# P14_ETH2_RGMII.net
KiCad netlist of a schematic drawn in Altium Designer
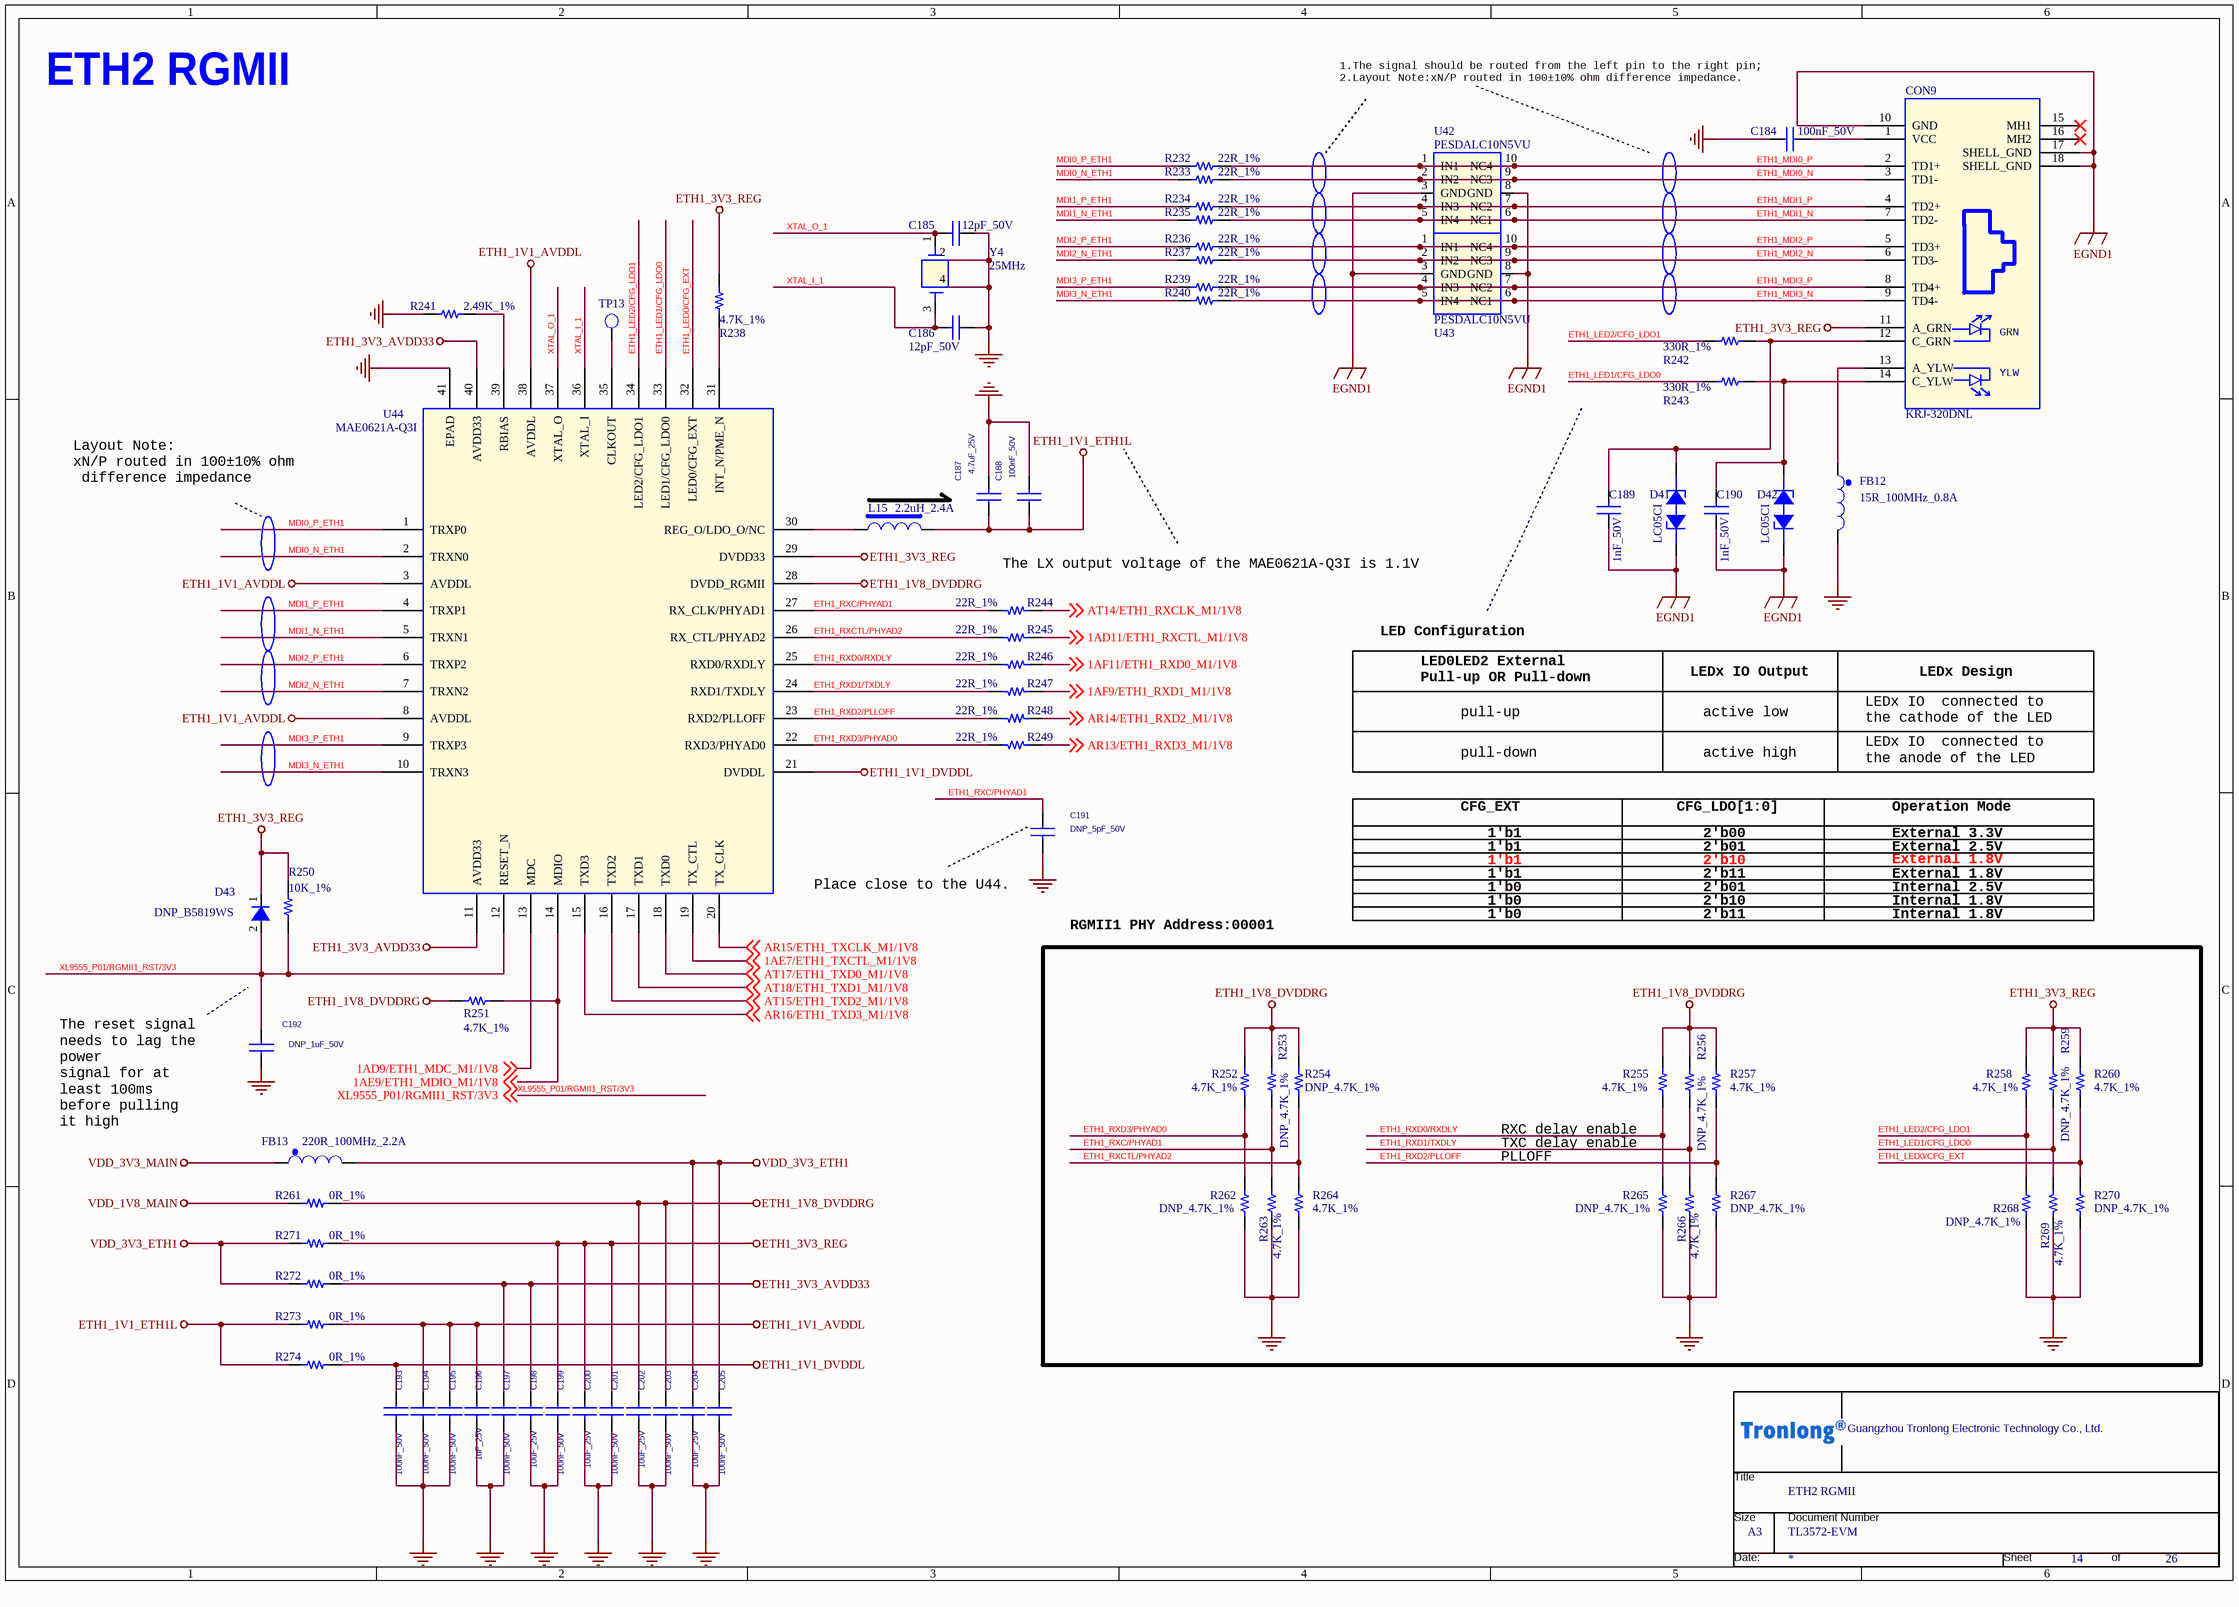
[diagram p0: P14_ETH2 RGMII.SchDoc]

(export (version "E")
  (design (tool "Eeschema 10.0.6"))
  (components
    (comp (ref "*")
      (value "Tronlong_TITTLE_20211115")
      (fields
        (field (name "DOC") "TL3572-EVM")
        (field (name "TITLE") "ETH2 RGMII")
        (field (name "ORGNAME") "Guangzhou Tronlong Electronic Technology Co., Ltd.")
        (field (name "PAGE SIZE") "A3")
        (field (name "PAGE NUMBER") "14")
        (field (name "PAGE COUNT") "26")
      )
      (libsource (lib "*") (part "Tronlong_TITTLE_20211115"))
    )
    (comp (ref "C184")
      (value "100nF_50V")
      (footprint "C0402")
      (description "贴片陶瓷电容,100nF,10%,50V,X7R")
      (fields
        (field (name "MANUFACTURER PARTNUMBER") "0402B104K500NT")
        (field (name "MANUFACTURER") "广东风华高新科技股份有限公司（FH）")
      )
      (libsource (lib "*") (part "CAP NP_Dup2"))
    )
    (comp (ref "C185")
      (value "12pF_50V")
      (footprint "C0402")
      (description "贴片陶瓷电容,12pF,5%,50V,COG")
      (fields
        (field (name "MANUFACTURER") "广东风华高新科技股份有限公司（FH）")
        (field (name "MANUFACTURER PARTNUMBER") "0402CG120J500NT")
      )
      (libsource (lib "*") (part "CAP NP_Dup2"))
    )
    (comp (ref "C186")
      (value "12pF_50V")
      (footprint "C0402")
      (description "贴片陶瓷电容,12pF,5%,50V,COG")
      (fields
        (field (name "MANUFACTURER PARTNUMBER") "0402CG120J500NT")
        (field (name "MANUFACTURER") "广东风华高新科技股份有限公司（FH）")
      )
      (libsource (lib "*") (part "CAP NP_Dup2"))
    )
    (comp (ref "C187")
      (value "4.7uF_25V")
      (footprint "C0603")
      (description "贴片陶瓷电容,4.7uF,10%,25V,X5R")
      (fields
        (field (name "MANUFACTURER PARTNUMBER") "0603X475K250NT")
        (field (name "MANUFACTURER") "广东风华高新科技股份有限公司（FH）")
      )
      (libsource (lib "*") (part "CAP NP_Dup2"))
    )
    (comp (ref "C188")
      (value "100nF_50V")
      (footprint "C0402")
      (description "贴片陶瓷电容,100nF,10%,50V,X7R")
      (fields
        (field (name "MANUFACTURER") "广东风华高新科技股份有限公司（FH）")
        (field (name "MANUFACTURER PARTNUMBER") "0402B104K500NT")
      )
      (libsource (lib "*") (part "CAP NP_Dup2"))
    )
    (comp (ref "C189")
      (value "1nF_50V")
      (footprint "C0402")
      (description "贴片陶瓷电容,1nF,10%,50V,X7R")
      (fields
        (field (name "TOLERANCE") "±10%")
        (field (name "MANUFACTURER") "广东风华高新科技股份有限公司（FH）")
        (field (name "CREATED BY") "JJJ")
      )
      (libsource (lib "*") (part "CAP NP_1"))
    )
    (comp (ref "C190")
      (value "1nF_50V")
      (footprint "C0402")
      (description "贴片陶瓷电容,1nF,10%,50V,X7R")
      (fields
        (field (name "TOLERANCE") "±10%")
        (field (name "MANUFACTURER") "广东风华高新科技股份有限公司（FH）")
        (field (name "CREATED BY") "JJJ")
      )
      (libsource (lib "*") (part "CAP NP_1"))
    )
    (comp (ref "C191")
      (value "DNP_5pF_50V")
      (footprint "C0402")
      (description "贴片陶瓷电容,22pF,5%,50V,COG")
      (fields
        (field (name "MANUFACTURER PARTNUMBER") "0402CG220J500NT")
        (field (name "MANUFACTURER") "广东风华高新科技股份有限公司（FH）")
      )
      (libsource (lib "*") (part "CAP NP_Dup2"))
    )
    (comp (ref "C192")
      (value "DNP_1uF_50V")
      (footprint "C0603")
      (description "贴片陶瓷电容,1uF,10%,50V,X5R")
      (fields
        (field (name "MANUFACTURER PARTNUMBER") "0603X105K500NT")
        (field (name "MANUFACTURER") "广东风华高新科技股份有限公司（FH）")
      )
      (libsource (lib "*") (part "CAP NP_Dup2"))
    )
    (comp (ref "C193")
      (value "100nF_50V")
      (footprint "C0402")
      (description "贴片陶瓷电容,100nF,10%,50V,X7R")
      (fields
        (field (name "MANUFACTURER") "广东风华高新科技股份有限公司（FH）")
        (field (name "MANUFACTURER PARTNUMBER") "0402B104K500NT")
      )
      (libsource (lib "*") (part "CAP NP_Dup2"))
    )
    (comp (ref "C194")
      (value "100nF_50V")
      (footprint "C0402")
      (description "贴片陶瓷电容,100nF,10%,50V,X7R")
      (fields
        (field (name "MANUFACTURER PARTNUMBER") "0402B104K500NT")
        (field (name "MANUFACTURER") "广东风华高新科技股份有限公司（FH）")
      )
      (libsource (lib "*") (part "CAP NP_Dup2"))
    )
    (comp (ref "C195")
      (value "100nF_50V")
      (footprint "C0402")
      (description "贴片陶瓷电容,100nF,10%,50V,X7R")
      (fields
        (field (name "MANUFACTURER") "广东风华高新科技股份有限公司（FH）")
        (field (name "MANUFACTURER PARTNUMBER") "0402B104K500NT")
      )
      (libsource (lib "*") (part "CAP NP_Dup2"))
    )
    (comp (ref "C196")
      (value "1uF_25V")
      (footprint "C0402")
      (description "贴片陶瓷电容,1uF,10%,25V,X5R")
      (fields
        (field (name "MANUFACTURER") "广东风华高新科技股份有限公司（FH）")
        (field (name "MANUFACTURER PARTNUMBER") "0402X105K250NT")
      )
      (libsource (lib "*") (part "CAP NP_Dup2"))
    )
    (comp (ref "C197")
      (value "100nF_50V")
      (footprint "C0402")
      (description "贴片陶瓷电容,100nF,10%,50V,X7R")
      (fields
        (field (name "MANUFACTURER") "广东风华高新科技股份有限公司（FH）")
        (field (name "MANUFACTURER PARTNUMBER") "0402B104K500NT")
      )
      (libsource (lib "*") (part "CAP NP_Dup2"))
    )
    (comp (ref "C198")
      (value "10uF_25V")
      (footprint "C0603")
      (description "贴片陶瓷电容,10uF,20%,25V,X5R")
      (fields
        (field (name "MANUFACTURER PARTNUMBER") "0603X106M250NT")
        (field (name "MANUFACTURER") "广东风华高新科技股份有限公司（FH）")
      )
      (libsource (lib "*") (part "CAP NP_Dup2"))
    )
    (comp (ref "C199")
      (value "100nF_50V")
      (footprint "C0402")
      (description "贴片陶瓷电容,100nF,10%,50V,X7R")
      (fields
        (field (name "MANUFACTURER") "广东风华高新科技股份有限公司（FH）")
        (field (name "MANUFACTURER PARTNUMBER") "0402B104K500NT")
      )
      (libsource (lib "*") (part "CAP NP_Dup2"))
    )
    (comp (ref "C200")
      (value "10uF_25V")
      (footprint "C0603")
      (description "贴片陶瓷电容,10uF,20%,25V,X5R")
      (fields
        (field (name "MANUFACTURER") "广东风华高新科技股份有限公司（FH）")
        (field (name "MANUFACTURER PARTNUMBER") "0603X106M250NT")
      )
      (libsource (lib "*") (part "CAP NP_Dup2"))
    )
    (comp (ref "C201")
      (value "100nF_50V")
      (footprint "C0402")
      (description "贴片陶瓷电容,100nF,10%,50V,X7R")
      (fields
        (field (name "MANUFACTURER PARTNUMBER") "0402B104K500NT")
        (field (name "MANUFACTURER") "广东风华高新科技股份有限公司（FH）")
      )
      (libsource (lib "*") (part "CAP NP_Dup2"))
    )
    (comp (ref "C202")
      (value "10uF_25V")
      (footprint "C0603")
      (description "贴片陶瓷电容,10uF,20%,25V,X5R")
      (fields
        (field (name "MANUFACTURER PARTNUMBER") "0603X106M250NT")
        (field (name "MANUFACTURER") "广东风华高新科技股份有限公司（FH）")
      )
      (libsource (lib "*") (part "CAP NP_Dup2"))
    )
    (comp (ref "C203")
      (value "100nF_50V")
      (footprint "C0402")
      (description "贴片陶瓷电容,100nF,10%,50V,X7R")
      (fields
        (field (name "MANUFACTURER") "广东风华高新科技股份有限公司（FH）")
        (field (name "MANUFACTURER PARTNUMBER") "0402B104K500NT")
      )
      (libsource (lib "*") (part "CAP NP_Dup2"))
    )
    (comp (ref "C204")
      (value "10uF_25V")
      (footprint "C0603")
      (description "贴片陶瓷电容,10uF,20%,25V,X5R")
      (fields
        (field (name "MANUFACTURER") "广东风华高新科技股份有限公司（FH）")
        (field (name "MANUFACTURER PARTNUMBER") "0603X106M250NT")
      )
      (libsource (lib "*") (part "CAP NP_Dup2"))
    )
    (comp (ref "C205")
      (value "100nF_50V")
      (footprint "C0402")
      (description "贴片陶瓷电容,100nF,10%,50V,X7R")
      (fields
        (field (name "MANUFACTURER") "广东风华高新科技股份有限公司（FH）")
        (field (name "MANUFACTURER PARTNUMBER") "0402B104K500NT")
      )
      (libsource (lib "*") (part "CAP NP_Dup2"))
    )
    (comp (ref "CON9")
      (value "KRJ-320DNL")
      (footprint "KRJ-320DNL_14P")
      (description "RJ45连接器,14P,2.54mm间距,单层母座,90度,插件")
      (fields (field (name "MANUFACTURER") "东莞市科优达电子科技有限公司（DGKYD）"))
      (libsource (lib "*") (part "KRJ-320DNL_0"))
    )
    (comp (ref "D41")
      (value "LC05CI")
      (footprint "SOD323")
      (description "TVS二极管,VRWM=5V,VBR=6V,一组,双向,30KV,30KV")
      (fields
        (field (name "MANUFACTURER PART NUMBER") "PESD3V3L1BA")
        (field (name "MANUFACTURER") "上海雷卯电子科技有限公司（Leiditech）")
      )
      (libsource (lib "*") (part "DIODE BREAKDOWN_2"))
    )
    (comp (ref "D42")
      (value "LC05CI")
      (footprint "SOD323")
      (description "TVS二极管,VRWM=5V,VBR=6V,一组,双向,30KV,30KV")
      (fields
        (field (name "MANUFACTURER") "上海雷卯电子科技有限公司（Leiditech）")
        (field (name "MANUFACTURER PART NUMBER") "PESD3V3L1BA")
      )
      (libsource (lib "*") (part "DIODE BREAKDOWN_2"))
    )
    (comp (ref "D43")
      (value "DNP_B5819WS")
      (footprint "SOD-323")
      (description "肖特基二极管,VR=40V,IF=1A,VF=0.6V@1A")
      (fields (field (name "TIINTPARTNUMBER") "1E0013") (field (name "MFR") "On Semiconductor"))
      (libsource (lib "*") (part "Diode200mA250V"))
    )
    (comp (ref "FB12")
      (value "15R_100MHz_0.8A")
      (footprint "L0603")
      (description "磁珠,100mΩ,0.8A,15R@100MHz")
      (fields
        (field (name "MANUFACTURER") "广东风华高新科技股份有限公司(FH)")
        (field (name "MANUFACTURER PARTNUMBER") "CBG160808U150T")
      )
      (libsource (lib "*") (part "FB_0"))
    )
    (comp (ref "FB13")
      (value "220R_100MHz_2.2A")
      (footprint "L0603")
      (description "磁珠,50mΩ,2.2A,220R@100MHz")
      (fields
        (field (name "MANUFACTURER PARTNUMBER") "UPZ1608U221-2R2TF")
        (field (name "MANUFACTURER") "深圳顺络电子股份有限公司（Sunlord）")
      )
      (libsource (lib "*") (part "FERRITE BEAD_Dup1"))
    )
    (comp (ref "L15")
      (value "2.2uH_2.4A")
      (footprint "SMD-L2520M-2P")
      (description "贴片功率电感,2.2uH,0.096Ω,Isat=2.9A,Irms=2.4A")
      (fields
        (field (name "MANUFACTURER") "深圳顺络电子股份有限公司(Sunlord)")
        (field (name "MANUFACTURER PARTNUMBER") "WPN252010U2R2MT")
      )
      (libsource (lib "*") (part "INDUCTOR"))
    )
    (comp (ref "R232")
      (value "22R_1%")
      (footprint "R0402")
      (description "贴片电阻,22R,±1%,1/16W")
      (fields
        (field (name "MANUFACTURER") "广东风华高新科技股份有限公司（FH）")
        (field (name "TOLERANCE") "5%")
        (field (name "CREATED BY") "YTL")
      )
      (libsource (lib "*") (part "Resistor_Dup1"))
    )
    (comp (ref "R233")
      (value "22R_1%")
      (footprint "R0402")
      (description "贴片电阻,22R,±1%,1/16W")
      (fields
        (field (name "MANUFACTURER") "广东风华高新科技股份有限公司（FH）")
        (field (name "TOLERANCE") "5%")
        (field (name "CREATED BY") "YTL")
      )
      (libsource (lib "*") (part "Resistor_Dup1"))
    )
    (comp (ref "R234")
      (value "22R_1%")
      (footprint "R0402")
      (description "贴片电阻,22R,±1%,1/16W")
      (fields
        (field (name "MANUFACTURER") "广东风华高新科技股份有限公司（FH）")
        (field (name "TOLERANCE") "5%")
        (field (name "CREATED BY") "YTL")
      )
      (libsource (lib "*") (part "Resistor_Dup1"))
    )
    (comp (ref "R235")
      (value "22R_1%")
      (footprint "R0402")
      (description "贴片电阻,22R,±1%,1/16W")
      (fields
        (field (name "MANUFACTURER") "广东风华高新科技股份有限公司（FH）")
        (field (name "TOLERANCE") "5%")
        (field (name "CREATED BY") "YTL")
      )
      (libsource (lib "*") (part "Resistor_Dup1"))
    )
    (comp (ref "R236")
      (value "22R_1%")
      (footprint "R0402")
      (description "贴片电阻,22R,±1%,1/16W")
      (fields
        (field (name "MANUFACTURER") "广东风华高新科技股份有限公司（FH）")
        (field (name "TOLERANCE") "5%")
        (field (name "CREATED BY") "YTL")
      )
      (libsource (lib "*") (part "Resistor_Dup1"))
    )
    (comp (ref "R237")
      (value "22R_1%")
      (footprint "R0402")
      (description "贴片电阻,22R,±1%,1/16W")
      (fields
        (field (name "MANUFACTURER") "广东风华高新科技股份有限公司（FH）")
        (field (name "TOLERANCE") "5%")
        (field (name "CREATED BY") "YTL")
      )
      (libsource (lib "*") (part "Resistor_Dup1"))
    )
    (comp (ref "R238")
      (value "4.7K_1%")
      (footprint "R0402")
      (description "贴片电阻,4.7K,±1%,1/16W")
      (fields
        (field (name "MANUFACTURER PARTNUMBER") "RC-02K4701FT")
        (field (name "MANUFACTURER") "广东风华高新科技股份有限公司（FH）")
      )
      (libsource (lib "*") (part "Resistor_Dup3"))
    )
    (comp (ref "R239")
      (value "22R_1%")
      (footprint "R0402")
      (description "贴片电阻,22R,±1%,1/16W")
      (fields
        (field (name "MANUFACTURER") "广东风华高新科技股份有限公司（FH）")
        (field (name "TOLERANCE") "5%")
        (field (name "CREATED BY") "YTL")
      )
      (libsource (lib "*") (part "Resistor_Dup1"))
    )
    (comp (ref "R240")
      (value "22R_1%")
      (footprint "R0402")
      (description "贴片电阻,22R,±1%,1/16W")
      (fields
        (field (name "MANUFACTURER") "广东风华高新科技股份有限公司（FH）")
        (field (name "TOLERANCE") "5%")
        (field (name "CREATED BY") "YTL")
      )
      (libsource (lib "*") (part "Resistor_Dup1"))
    )
    (comp (ref "R241")
      (value "2.49K_1%")
      (footprint "R0603")
      (description "贴片电阻,2.49K,±1%,1/10W")
      (fields
        (field (name "MANUFACTURER") "广东风华高新科技股份有限公司（FH）")
        (field (name "MANUFACTURER PARTNUMBER") "RS-03K2491FT")
      )
      (libsource (lib "*") (part "Resistor_Dup3"))
    )
    (comp (ref "R242")
      (value "330R_1%")
      (footprint "R0402")
      (description "RC0402FR-07330RL,0402WGF3300TCE")
      (fields
        (field (name "MANUFACTURER PARTNUMBER") "330R,±1%,R0402,≥1/16W")
        (field (name "MANUFACTURER") "广州创龙")
      )
      (libsource (lib "*") (part "Resistor_Dup3"))
    )
    (comp (ref "R243")
      (value "330R_1%")
      (footprint "R0402")
      (description "RC0402FR-07330RL,0402WGF3300TCE")
      (fields
        (field (name "MANUFACTURER") "广州创龙")
        (field (name "MANUFACTURER PARTNUMBER") "330R,±1%,R0402,≥1/16W")
      )
      (libsource (lib "*") (part "Resistor_Dup3"))
    )
    (comp (ref "R244")
      (value "22R_1%")
      (footprint "R0402")
      (description "贴片电阻,22R,±1%,1/16W")
      (fields
        (field (name "MANUFACTURER PARTNUMBER") "RC-02K22R0FT")
        (field (name "MANUFACTURER") "广东风华高新科技股份有限公司（FH）")
      )
      (libsource (lib "*") (part "Resistor_Dup3"))
    )
    (comp (ref "R245")
      (value "22R_1%")
      (footprint "R0402")
      (description "贴片电阻,22R,±1%,1/16W")
      (fields
        (field (name "MANUFACTURER") "广东风华高新科技股份有限公司（FH）")
        (field (name "MANUFACTURER PARTNUMBER") "RC-02K22R0FT")
      )
      (libsource (lib "*") (part "Resistor_Dup3"))
    )
    (comp (ref "R246")
      (value "22R_1%")
      (footprint "R0402")
      (description "贴片电阻,22R,±1%,1/16W")
      (fields
        (field (name "MANUFACTURER") "广东风华高新科技股份有限公司（FH）")
        (field (name "MANUFACTURER PARTNUMBER") "RC-02K22R0FT")
      )
      (libsource (lib "*") (part "Resistor_Dup3"))
    )
    (comp (ref "R247")
      (value "22R_1%")
      (footprint "R0402")
      (description "贴片电阻,22R,±1%,1/16W")
      (fields
        (field (name "MANUFACTURER") "广东风华高新科技股份有限公司（FH）")
        (field (name "MANUFACTURER PARTNUMBER") "RC-02K22R0FT")
      )
      (libsource (lib "*") (part "Resistor_Dup3"))
    )
    (comp (ref "R248")
      (value "22R_1%")
      (footprint "R0402")
      (description "贴片电阻,22R,±1%,1/16W")
      (fields
        (field (name "MANUFACTURER") "广东风华高新科技股份有限公司（FH）")
        (field (name "MANUFACTURER PARTNUMBER") "RC-02K22R0FT")
      )
      (libsource (lib "*") (part "Resistor_Dup3"))
    )
    (comp (ref "R249")
      (value "22R_1%")
      (footprint "R0402")
      (description "贴片电阻,22R,±1%,1/16W")
      (fields
        (field (name "MANUFACTURER PARTNUMBER") "RC-02K22R0FT")
        (field (name "MANUFACTURER") "广东风华高新科技股份有限公司（FH）")
      )
      (libsource (lib "*") (part "Resistor_Dup3"))
    )
    (comp (ref "R250")
      (value "10K_1%")
      (footprint "R0402")
      (description "贴片电阻,10K,±1%,1/16W")
      (fields
        (field (name "MANUFACTURER PARTNUMBER") "RC-02K1002FT")
        (field (name "MANUFACTURER") "广东风华高新科技股份有限公司（FH）")
      )
      (libsource (lib "*") (part "Resistor_Dup3"))
    )
    (comp (ref "R251")
      (value "4.7K_1%")
      (footprint "R0402")
      (description "贴片电阻,4.7K,±1%,1/16W")
      (fields
        (field (name "MANUFACTURER PARTNUMBER") "RC-02K4701FT")
        (field (name "MANUFACTURER") "广东风华高新科技股份有限公司（FH）")
      )
      (libsource (lib "*") (part "Resistor_Dup3"))
    )
    (comp (ref "R252")
      (value "4.7K_1%")
      (footprint "R0402")
      (description "贴片电阻,4.7K,±1%,1/16W")
      (fields
        (field (name "MANUFACTURER PARTNUMBER") "RC-02K4701FT")
        (field (name "MANUFACTURER") "广东风华高新科技股份有限公司（FH）")
      )
      (libsource (lib "*") (part "Resistor_Dup3"))
    )
    (comp (ref "R253")
      (value "DNP_4.7K_1%")
      (footprint "R0402")
      (description "RC0402FR-074K7L,0402WGF4701TCE")
      (fields
        (field (name "MANUFACTURER") "广州创龙")
        (field (name "MANUFACTURER PARTNUMBER") "4.7K,±1%,R0402,≥1/16W")
      )
      (libsource (lib "*") (part "Resistor_Dup3"))
    )
    (comp (ref "R254")
      (value "DNP_4.7K_1%")
      (footprint "R0402")
      (description "RC0402FR-074K7L,0402WGF4701TCE")
      (fields
        (field (name "MANUFACTURER PARTNUMBER") "4.7K,±1%,R0402,≥1/16W")
        (field (name "MANUFACTURER") "广州创龙")
      )
      (libsource (lib "*") (part "Resistor_Dup3"))
    )
    (comp (ref "R255")
      (value "4.7K_1%")
      (footprint "R0402")
      (description "贴片电阻,4.7K,±1%,1/16W")
      (fields
        (field (name "MANUFACTURER PARTNUMBER") "RC-02K4701FT")
        (field (name "MANUFACTURER") "广东风华高新科技股份有限公司（FH）")
      )
      (libsource (lib "*") (part "Resistor_Dup3"))
    )
    (comp (ref "R256")
      (value "DNP_4.7K_1%")
      (footprint "R0402")
      (description "RC0402FR-074K7L,0402WGF4701TCE")
      (fields
        (field (name "MANUFACTURER PARTNUMBER") "4.7K,±1%,R0402,≥1/16W")
        (field (name "MANUFACTURER") "广州创龙")
      )
      (libsource (lib "*") (part "Resistor_Dup3"))
    )
    (comp (ref "R257")
      (value "4.7K_1%")
      (footprint "R0402")
      (description "贴片电阻,4.7K,±1%,1/16W")
      (fields
        (field (name "MANUFACTURER") "广东风华高新科技股份有限公司（FH）")
        (field (name "MANUFACTURER PARTNUMBER") "RC-02K4701FT")
      )
      (libsource (lib "*") (part "Resistor_Dup3"))
    )
    (comp (ref "R258")
      (value "4.7K_1%")
      (footprint "R0402")
      (description "贴片电阻,4.7K,±1%,1/16W")
      (fields
        (field (name "MANUFACTURER") "广东风华高新科技股份有限公司（FH）")
        (field (name "MANUFACTURER PARTNUMBER") "RC-02K4701FT")
      )
      (libsource (lib "*") (part "Resistor_Dup3"))
    )
    (comp (ref "R259")
      (value "DNP_4.7K_1%")
      (footprint "R0402")
      (description "RC0402FR-074K7L,0402WGF4701TCE")
      (fields
        (field (name "MANUFACTURER PARTNUMBER") "4.7K,±1%,R0402,≥1/16W")
        (field (name "MANUFACTURER") "广州创龙")
      )
      (libsource (lib "*") (part "Resistor_Dup3"))
    )
    (comp (ref "R260")
      (value "4.7K_1%")
      (footprint "R0402")
      (description "贴片电阻,4.7K,±1%,1/16W")
      (fields
        (field (name "MANUFACTURER") "广东风华高新科技股份有限公司（FH）")
        (field (name "MANUFACTURER PARTNUMBER") "RC-02K4701FT")
      )
      (libsource (lib "*") (part "Resistor_Dup3"))
    )
    (comp (ref "R261")
      (value "0R_1%")
      (footprint "R0603")
      (description "贴片电阻,0R,±1%,1/10W")
      (fields
        (field (name "MANUFACTURER PARTNUMBER") "RS-03000FT")
        (field (name "MANUFACTURER") "广东风华高新科技股份有限公司（FH）")
      )
      (libsource (lib "*") (part "Resistor_Dup3"))
    )
    (comp (ref "R262")
      (value "DNP_4.7K_1%")
      (footprint "R0402")
      (description "RC0402FR-074K7L,0402WGF4701TCE")
      (fields
        (field (name "MANUFACTURER PARTNUMBER") "4.7K,±1%,R0402,≥1/16W")
        (field (name "MANUFACTURER") "广州创龙")
      )
      (libsource (lib "*") (part "Resistor_Dup3"))
    )
    (comp (ref "R263")
      (value "4.7K_1%")
      (footprint "R0402")
      (description "贴片电阻,4.7K,±1%,1/16W")
      (fields
        (field (name "MANUFACTURER PARTNUMBER") "RC-02K4701FT")
        (field (name "MANUFACTURER") "广东风华高新科技股份有限公司（FH）")
      )
      (libsource (lib "*") (part "Resistor_Dup3"))
    )
    (comp (ref "R264")
      (value "4.7K_1%")
      (footprint "R0402")
      (description "贴片电阻,4.7K,±1%,1/16W")
      (fields
        (field (name "MANUFACTURER") "广东风华高新科技股份有限公司（FH）")
        (field (name "MANUFACTURER PARTNUMBER") "RC-02K4701FT")
      )
      (libsource (lib "*") (part "Resistor_Dup3"))
    )
    (comp (ref "R265")
      (value "DNP_4.7K_1%")
      (footprint "R0402")
      (description "RC0402FR-074K7L,0402WGF4701TCE")
      (fields
        (field (name "MANUFACTURER") "广州创龙")
        (field (name "MANUFACTURER PARTNUMBER") "4.7K,±1%,R0402,≥1/16W")
      )
      (libsource (lib "*") (part "Resistor_Dup3"))
    )
    (comp (ref "R266")
      (value "4.7K_1%")
      (footprint "R0402")
      (description "贴片电阻,4.7K,±1%,1/16W")
      (fields
        (field (name "MANUFACTURER") "广东风华高新科技股份有限公司（FH）")
        (field (name "MANUFACTURER PARTNUMBER") "RC-02K4701FT")
      )
      (libsource (lib "*") (part "Resistor_Dup3"))
    )
    (comp (ref "R267")
      (value "DNP_4.7K_1%")
      (footprint "R0402")
      (description "RC0402FR-074K7L,0402WGF4701TCE")
      (fields
        (field (name "MANUFACTURER") "广州创龙")
        (field (name "MANUFACTURER PARTNUMBER") "4.7K,±1%,R0402,≥1/16W")
      )
      (libsource (lib "*") (part "Resistor_Dup3"))
    )
    (comp (ref "R268")
      (value "DNP_4.7K_1%")
      (footprint "R0402")
      (description "RC0402FR-074K7L,0402WGF4701TCE")
      (fields
        (field (name "MANUFACTURER PARTNUMBER") "4.7K,±1%,R0402,≥1/16W")
        (field (name "MANUFACTURER") "广州创龙")
      )
      (libsource (lib "*") (part "Resistor_Dup3"))
    )
    (comp (ref "R269")
      (value "4.7K_1%")
      (footprint "R0402")
      (description "贴片电阻,4.7K,±1%,1/16W")
      (fields
        (field (name "MANUFACTURER PARTNUMBER") "RC-02K4701FT")
        (field (name "MANUFACTURER") "广东风华高新科技股份有限公司（FH）")
      )
      (libsource (lib "*") (part "Resistor_Dup3"))
    )
    (comp (ref "R270")
      (value "DNP_4.7K_1%")
      (footprint "R0402")
      (description "RC0402FR-074K7L,0402WGF4701TCE")
      (fields
        (field (name "MANUFACTURER PARTNUMBER") "4.7K,±1%,R0402,≥1/16W")
        (field (name "MANUFACTURER") "广州创龙")
      )
      (libsource (lib "*") (part "Resistor_Dup3"))
    )
    (comp (ref "R271")
      (value "0R_1%")
      (footprint "R0603")
      (description "贴片电阻,0R,±1%,1/10W")
      (fields
        (field (name "MANUFACTURER") "广东风华高新科技股份有限公司（FH）")
        (field (name "MANUFACTURER PARTNUMBER") "RS-03000FT")
      )
      (libsource (lib "*") (part "Resistor_Dup3"))
    )
    (comp (ref "R272")
      (value "0R_1%")
      (footprint "R0603")
      (description "贴片电阻,0R,±1%,1/10W")
      (fields
        (field (name "MANUFACTURER") "广东风华高新科技股份有限公司（FH）")
        (field (name "MANUFACTURER PARTNUMBER") "RS-03000FT")
      )
      (libsource (lib "*") (part "Resistor_Dup3"))
    )
    (comp (ref "R273")
      (value "0R_1%")
      (footprint "R0603")
      (description "贴片电阻,0R,±1%,1/10W")
      (fields
        (field (name "MANUFACTURER PARTNUMBER") "RS-03000FT")
        (field (name "MANUFACTURER") "广东风华高新科技股份有限公司（FH）")
      )
      (libsource (lib "*") (part "Resistor_Dup3"))
    )
    (comp (ref "R274")
      (value "0R_1%")
      (footprint "R0603")
      (description "贴片电阻,0R,±1%,1/10W")
      (fields
        (field (name "MANUFACTURER") "广东风华高新科技股份有限公司（FH）")
        (field (name "MANUFACTURER PARTNUMBER") "RS-03000FT")
      )
      (libsource (lib "*") (part "Resistor_Dup3"))
    )
    (comp (ref "TP13")
      (value "SMT TP")
      (footprint "TP30")
      (description "/")
      (libsource (lib "*") (part "T POINT R"))
    )
    (comp (ref "U42")
      (value "PESDALC10N5VU")
      (footprint "DFN-10-2510")
      (description "ESD二极管,VRWM=5V,VBR=6V,四组,单向,15KV,30KV")
      (fields (field (name "MANUFACTURER") "上海芯导电子科技股份有限公司（Prisemi）"))
      (libsource (lib "*") (part "SU099PGTR"))
    )
    (comp (ref "U43")
      (value "PESDALC10N5VU")
      (footprint "DFN-10-2510")
      (description "ESD二极管,VRWM=5V,VBR=6V,四组,单向,15KV,30KV")
      (fields (field (name "MANUFACTURER") "上海芯导电子科技股份有限公司（Prisemi）"))
      (libsource (lib "*") (part "SU099PGTR"))
    )
    (comp (ref "U44")
      (value "MAE0621A-Q3I")
      (footprint "QFN40_5x5")
      (description "以太网收发器，RGMII/GMII/MII")
      (fields (field (name "MANUFACTURER") "联芸科技（杭州）股份有限公司"))
      (libsource (lib "*") (part "YT8531H-CA"))
    )
    (comp (ref "Y4")
      (value "25MHz")
      (footprint "SMD_3225")
      (description "四脚无源晶振,25MHz,±10ppm,12pF,30Ω,±30ppm")
      (fields
        (field (name "MANUFACTURER PARTNUMBER") "S3B25.000F1210F30")
        (field (name "MANUFACTURER") "深圳市星通时频电子有限公司（SCTF）")
      )
      (libsource (lib "*") (part "CRYSTAL-4 PIN"))
    )
  )
  (nets
    (net (code "1") (name "/ETH1_LED0{slash}CFG_EXT") (class "Default")
      (node (ref "R260") (pin "1") (pinfunction "1_1") (pintype "passive"))
      (node (ref "R270") (pin "2") (pinfunction "2_2") (pintype "passive"))
      (node (ref "U44") (pin "32") (pinfunction "LED0/CFG_EXT_32") (pintype "passive"))
    )
    (net (code "2") (name "/ETH1_LED1{slash}CFG_LDO0") (class "Default")
      (node (ref "R243") (pin "1") (pinfunction "1_1") (pintype "passive"))
      (node (ref "R259") (pin "1") (pinfunction "1_1") (pintype "passive"))
      (node (ref "R269") (pin "2") (pinfunction "2_2") (pintype "passive"))
      (node (ref "U44") (pin "33") (pinfunction "LED1/CFG_LDO0_33") (pintype "passive"))
    )
    (net (code "3") (name "/ETH1_LED2{slash}CFG_LDO1") (class "Default")
      (node (ref "R242") (pin "1") (pinfunction "1_1") (pintype "passive"))
      (node (ref "R258") (pin "1") (pinfunction "1_1") (pintype "passive"))
      (node (ref "R268") (pin "2") (pinfunction "2_2") (pintype "passive"))
      (node (ref "U44") (pin "34") (pinfunction "LED2/CFG_LDO1_34") (pintype "passive"))
    )
    (net (code "4") (name "/ETH1_MDI0_N") (class "Default")
      (node (ref "CON9") (pin "3") (pinfunction "TD1-_3") (pintype "passive"))
      (node (ref "R233") (pin "2") (pinfunction "2_2") (pintype "passive"))
      (node (ref "U42") (pin "2") (pinfunction "IN2_2") (pintype "passive"))
      (node (ref "U42") (pin "9") (pinfunction "NC3_9") (pintype "passive"))
    )
    (net (code "5") (name "/ETH1_MDI0_P") (class "Default")
      (node (ref "CON9") (pin "2") (pinfunction "TD1+_2") (pintype "passive"))
      (node (ref "R232") (pin "2") (pinfunction "2_2") (pintype "passive"))
      (node (ref "U42") (pin "1") (pinfunction "IN1_1") (pintype "passive"))
      (node (ref "U42") (pin "10") (pinfunction "NC4_10") (pintype "passive"))
    )
    (net (code "6") (name "/ETH1_MDI1_N") (class "Default")
      (node (ref "CON9") (pin "7") (pinfunction "TD2-_7") (pintype "passive"))
      (node (ref "R235") (pin "2") (pinfunction "2_2") (pintype "passive"))
      (node (ref "U42") (pin "5") (pinfunction "IN4_5") (pintype "passive"))
      (node (ref "U42") (pin "6") (pinfunction "NC1_6") (pintype "passive"))
    )
    (net (code "7") (name "/ETH1_MDI1_P") (class "Default")
      (node (ref "CON9") (pin "4") (pinfunction "TD2+_4") (pintype "passive"))
      (node (ref "R234") (pin "2") (pinfunction "2_2") (pintype "passive"))
      (node (ref "U42") (pin "4") (pinfunction "IN3_4") (pintype "passive"))
      (node (ref "U42") (pin "7") (pinfunction "NC2_7") (pintype "passive"))
    )
    (net (code "8") (name "/ETH1_MDI2_N") (class "Default")
      (node (ref "CON9") (pin "6") (pinfunction "TD3-_6") (pintype "passive"))
      (node (ref "R237") (pin "2") (pinfunction "2_2") (pintype "passive"))
      (node (ref "U43") (pin "2") (pinfunction "IN2_2") (pintype "passive"))
      (node (ref "U43") (pin "9") (pinfunction "NC3_9") (pintype "passive"))
    )
    (net (code "9") (name "/ETH1_MDI2_P") (class "Default")
      (node (ref "CON9") (pin "5") (pinfunction "TD3+_5") (pintype "passive"))
      (node (ref "R236") (pin "2") (pinfunction "2_2") (pintype "passive"))
      (node (ref "U43") (pin "1") (pinfunction "IN1_1") (pintype "passive"))
      (node (ref "U43") (pin "10") (pinfunction "NC4_10") (pintype "passive"))
    )
    (net (code "10") (name "/ETH1_MDI3_N") (class "Default")
      (node (ref "CON9") (pin "9") (pinfunction "TD4-_9") (pintype "passive"))
      (node (ref "R240") (pin "2") (pinfunction "2_2") (pintype "passive"))
      (node (ref "U43") (pin "5") (pinfunction "IN4_5") (pintype "passive"))
      (node (ref "U43") (pin "6") (pinfunction "NC1_6") (pintype "passive"))
    )
    (net (code "11") (name "/ETH1_MDI3_P") (class "Default")
      (node (ref "CON9") (pin "8") (pinfunction "TD4+_8") (pintype "passive"))
      (node (ref "R239") (pin "2") (pinfunction "2_2") (pintype "passive"))
      (node (ref "U43") (pin "4") (pinfunction "IN3_4") (pintype "passive"))
      (node (ref "U43") (pin "7") (pinfunction "NC2_7") (pintype "passive"))
    )
    (net (code "12") (name "/ETH1_RXCTL{slash}PHYAD2") (class "Default")
      (node (ref "R245") (pin "2") (pinfunction "2_2") (pintype "passive"))
      (node (ref "R254") (pin "1") (pinfunction "1_1") (pintype "passive"))
      (node (ref "R264") (pin "2") (pinfunction "2_2") (pintype "passive"))
      (node (ref "U44") (pin "26") (pinfunction "RX_CTL/PHYAD2_26") (pintype "passive"))
    )
    (net (code "13") (name "/ETH1_RXC{slash}PHYAD1") (class "Default")
      (node (ref "C191") (pin "1") (pinfunction "1_1") (pintype "passive"))
      (node (ref "R244") (pin "2") (pinfunction "2_2") (pintype "passive"))
      (node (ref "R253") (pin "1") (pinfunction "1_1") (pintype "passive"))
      (node (ref "R263") (pin "2") (pinfunction "2_2") (pintype "passive"))
      (node (ref "U44") (pin "27") (pinfunction "RX_CLK/PHYAD1_27") (pintype "passive"))
    )
    (net (code "14") (name "/ETH1_RXD0{slash}RXDLY") (class "Default")
      (node (ref "R246") (pin "2") (pinfunction "2_2") (pintype "passive"))
      (node (ref "R255") (pin "1") (pinfunction "1_1") (pintype "passive"))
      (node (ref "R265") (pin "2") (pinfunction "2_2") (pintype "passive"))
      (node (ref "U44") (pin "25") (pinfunction "RXD0/RXDLY_25") (pintype "passive"))
    )
    (net (code "15") (name "/ETH1_RXD1{slash}TXDLY") (class "Default")
      (node (ref "R247") (pin "2") (pinfunction "2_2") (pintype "passive"))
      (node (ref "R256") (pin "1") (pinfunction "1_1") (pintype "passive"))
      (node (ref "R266") (pin "2") (pinfunction "2_2") (pintype "passive"))
      (node (ref "U44") (pin "24") (pinfunction "RXD1/TXDLY_24") (pintype "passive"))
    )
    (net (code "16") (name "/ETH1_RXD2{slash}PLLOFF") (class "Default")
      (node (ref "R248") (pin "2") (pinfunction "2_2") (pintype "passive"))
      (node (ref "R257") (pin "1") (pinfunction "1_1") (pintype "passive"))
      (node (ref "R267") (pin "2") (pinfunction "2_2") (pintype "passive"))
      (node (ref "U44") (pin "23") (pinfunction "RXD2/PLLOFF_23") (pintype "passive"))
    )
    (net (code "17") (name "/ETH1_RXD3{slash}PHYAD0") (class "Default")
      (node (ref "R249") (pin "2") (pinfunction "2_2") (pintype "passive"))
      (node (ref "R252") (pin "1") (pinfunction "1_1") (pintype "passive"))
      (node (ref "R262") (pin "2") (pinfunction "2_2") (pintype "passive"))
      (node (ref "U44") (pin "22") (pinfunction "RXD3/PHYAD0_22") (pintype "passive"))
    )
    (net (code "18") (name "/MDI0_N_ETH1") (class "Default")
      (node (ref "R233") (pin "1") (pinfunction "1_1") (pintype "passive"))
      (node (ref "U44") (pin "2") (pinfunction "TRXN0_2") (pintype "passive"))
    )
    (net (code "19") (name "/MDI0_P_ETH1") (class "Default")
      (node (ref "R232") (pin "1") (pinfunction "1_1") (pintype "passive"))
      (node (ref "U44") (pin "1") (pinfunction "TRXP0_1") (pintype "passive"))
    )
    (net (code "20") (name "/MDI1_N_ETH1") (class "Default")
      (node (ref "R235") (pin "1") (pinfunction "1_1") (pintype "passive"))
      (node (ref "U44") (pin "5") (pinfunction "TRXN1_5") (pintype "passive"))
    )
    (net (code "21") (name "/MDI1_P_ETH1") (class "Default")
      (node (ref "R234") (pin "1") (pinfunction "1_1") (pintype "passive"))
      (node (ref "U44") (pin "4") (pinfunction "TRXP1_4") (pintype "passive"))
    )
    (net (code "22") (name "/MDI2_N_ETH1") (class "Default")
      (node (ref "R237") (pin "1") (pinfunction "1_1") (pintype "passive"))
      (node (ref "U44") (pin "7") (pinfunction "TRXN2_7") (pintype "passive"))
    )
    (net (code "23") (name "/MDI2_P_ETH1") (class "Default")
      (node (ref "R236") (pin "1") (pinfunction "1_1") (pintype "passive"))
      (node (ref "U44") (pin "6") (pinfunction "TRXP2_6") (pintype "passive"))
    )
    (net (code "24") (name "/MDI3_N_ETH1") (class "Default")
      (node (ref "R240") (pin "1") (pinfunction "1_1") (pintype "passive"))
      (node (ref "U44") (pin "10") (pinfunction "TRXN3_10") (pintype "passive"))
    )
    (net (code "25") (name "/MDI3_P_ETH1") (class "Default")
      (node (ref "R239") (pin "1") (pinfunction "1_1") (pintype "passive"))
      (node (ref "U44") (pin "9") (pinfunction "TRXP3_9") (pintype "passive"))
    )
    (net (code "26") (name "/XTAL_I_1") (class "Default")
      (node (ref "C186") (pin "2") (pinfunction "2_2") (pintype "passive"))
      (node (ref "U44") (pin "36") (pinfunction "XTAL_I_36") (pintype "passive"))
      (node (ref "Y4") (pin "3") (pinfunction "3_3") (pintype "passive"))
    )
    (net (code "27") (name "/XTAL_O_1") (class "Default")
      (node (ref "C185") (pin "2") (pinfunction "2_2") (pintype "passive"))
      (node (ref "U44") (pin "37") (pinfunction "XTAL_O_37") (pintype "passive"))
      (node (ref "Y4") (pin "1") (pinfunction "1_1") (pintype "passive"))
    )
    (net (code "28") (name "1AD9{slash}ETH1_MDC_M1{slash}1V8") (class "Default")
      (node (ref "U44") (pin "13") (pinfunction "MDC_13") (pintype "passive"))
    )
    (net (code "29") (name "1AD11{slash}ETH1_RXCTL_M1{slash}1V8") (class "Default")
      (node (ref "R245") (pin "1") (pinfunction "1_1") (pintype "passive"))
    )
    (net (code "30") (name "1AE7{slash}ETH1_TXCTL_M1{slash}1V8") (class "Default")
      (node (ref "U44") (pin "19") (pinfunction "TX_CTL_19") (pintype "passive"))
    )
    (net (code "31") (name "1AE9{slash}ETH1_MDIO_M1{slash}1V8") (class "Default")
      (node (ref "R251") (pin "2") (pinfunction "2_2") (pintype "passive"))
      (node (ref "U44") (pin "14") (pinfunction "MDIO_14") (pintype "passive"))
    )
    (net (code "32") (name "1AF9{slash}ETH1_RXD1_M1{slash}1V8") (class "Default")
      (node (ref "R247") (pin "1") (pinfunction "1_1") (pintype "passive"))
    )
    (net (code "33") (name "1AF11{slash}ETH1_RXD0_M1{slash}1V8") (class "Default")
      (node (ref "R246") (pin "1") (pinfunction "1_1") (pintype "passive"))
    )
    (net (code "34") (name "AR13{slash}ETH1_RXD3_M1{slash}1V8") (class "Default")
      (node (ref "R249") (pin "1") (pinfunction "1_1") (pintype "passive"))
    )
    (net (code "35") (name "AR14{slash}ETH1_RXD2_M1{slash}1V8") (class "Default")
      (node (ref "R248") (pin "1") (pinfunction "1_1") (pintype "passive"))
    )
    (net (code "36") (name "AR15{slash}ETH1_TXCLK_M1{slash}1V8") (class "Default")
      (node (ref "U44") (pin "20") (pinfunction "TX_CLK_20") (pintype "passive"))
    )
    (net (code "37") (name "AR16{slash}ETH1_TXD3_M1{slash}1V8") (class "Default")
      (node (ref "U44") (pin "15") (pinfunction "TXD3_15") (pintype "passive"))
    )
    (net (code "38") (name "AT14{slash}ETH1_RXCLK_M1{slash}1V8") (class "Default")
      (node (ref "R244") (pin "1") (pinfunction "1_1") (pintype "passive"))
    )
    (net (code "39") (name "AT15{slash}ETH1_TXD2_M1{slash}1V8") (class "Default")
      (node (ref "U44") (pin "16") (pinfunction "TXD2_16") (pintype "passive"))
    )
    (net (code "40") (name "AT17{slash}ETH1_TXD0_M1{slash}1V8") (class "Default")
      (node (ref "U44") (pin "18") (pinfunction "TXD0_18") (pintype "passive"))
    )
    (net (code "41") (name "AT18{slash}ETH1_TXD1_M1{slash}1V8") (class "Default")
      (node (ref "U44") (pin "17") (pinfunction "TXD1_17") (pintype "passive"))
    )
    (net (code "42") (name "EGND1") (class "Default")
      (node (ref "C189") (pin "1") (pinfunction "1_1") (pintype "passive"))
      (node (ref "C190") (pin "1") (pinfunction "1_1") (pintype "passive"))
      (node (ref "CON9") (pin "10") (pinfunction "GND_10") (pintype "passive"))
      (node (ref "CON9") (pin "17") (pinfunction "SHELL_GND_17") (pintype "power_in"))
      (node (ref "CON9") (pin "18") (pinfunction "SHELL_GND_18") (pintype "power_in"))
      (node (ref "D41") (pin "1") (pinfunction "ANODE1_1") (pintype "passive"))
      (node (ref "D42") (pin "1") (pinfunction "ANODE1_1") (pintype "passive"))
      (node (ref "U42") (pin "3") (pinfunction "GND_3") (pintype "power_in"))
      (node (ref "U42") (pin "8") (pinfunction "GND_8") (pintype "power_in"))
      (node (ref "U43") (pin "3") (pinfunction "GND_3") (pintype "power_in"))
      (node (ref "U43") (pin "8") (pinfunction "GND_8") (pintype "power_in"))
    )
    (net (code "43") (name "ETH1_1V1_AVDDL") (class "Default")
      (node (ref "C194") (pin "1") (pinfunction "1_1") (pintype "passive"))
      (node (ref "C195") (pin "1") (pinfunction "1_1") (pintype "passive"))
      (node (ref "C196") (pin "1") (pinfunction "1_1") (pintype "passive"))
      (node (ref "R273") (pin "2") (pinfunction "2_2") (pintype "passive"))
      (node (ref "U44") (pin "3") (pinfunction "AVDDL_3") (pintype "power_in"))
      (node (ref "U44") (pin "38") (pinfunction "AVDDL_38") (pintype "power_in"))
      (node (ref "U44") (pin "8") (pinfunction "AVDDL_8") (pintype "power_in"))
    )
    (net (code "44") (name "ETH1_1V1_DVDDL") (class "Default")
      (node (ref "C193") (pin "1") (pinfunction "1_1") (pintype "passive"))
      (node (ref "R274") (pin "2") (pinfunction "2_2") (pintype "passive"))
      (node (ref "U44") (pin "21") (pinfunction "DVDDL_21") (pintype "power_in"))
    )
    (net (code "45") (name "ETH1_1V1_ETH1L") (class "Default")
      (node (ref "C187") (pin "1") (pinfunction "1_1") (pintype "passive"))
      (node (ref "C188") (pin "1") (pinfunction "1_1") (pintype "passive"))
      (node (ref "L15") (pin "2") (pinfunction "2_2") (pintype "passive"))
      (node (ref "R273") (pin "1") (pinfunction "1_1") (pintype "passive"))
      (node (ref "R274") (pin "1") (pinfunction "1_1") (pintype "passive"))
    )
    (net (code "46") (name "ETH1_1V8_DVDDRG") (class "Default")
      (node (ref "C202") (pin "1") (pinfunction "1_1") (pintype "passive"))
      (node (ref "C203") (pin "1") (pinfunction "1_1") (pintype "passive"))
      (node (ref "R251") (pin "1") (pinfunction "1_1") (pintype "passive"))
      (node (ref "R252") (pin "2") (pinfunction "2_2") (pintype "passive"))
      (node (ref "R253") (pin "2") (pinfunction "2_2") (pintype "passive"))
      (node (ref "R254") (pin "2") (pinfunction "2_2") (pintype "passive"))
      (node (ref "R255") (pin "2") (pinfunction "2_2") (pintype "passive"))
      (node (ref "R256") (pin "2") (pinfunction "2_2") (pintype "passive"))
      (node (ref "R257") (pin "2") (pinfunction "2_2") (pintype "passive"))
      (node (ref "R261") (pin "2") (pinfunction "2_2") (pintype "passive"))
      (node (ref "U44") (pin "28") (pinfunction "DVDD_RGMII_28") (pintype "power_in"))
    )
    (net (code "47") (name "ETH1_3V3_AVDD33") (class "Default")
      (node (ref "C197") (pin "1") (pinfunction "1_1") (pintype "passive"))
      (node (ref "C198") (pin "1") (pinfunction "1_1") (pintype "passive"))
      (node (ref "R272") (pin "2") (pinfunction "2_2") (pintype "passive"))
      (node (ref "U44") (pin "11") (pinfunction "AVDD33_11") (pintype "power_in"))
      (node (ref "U44") (pin "40") (pinfunction "AVDD33_40") (pintype "power_in"))
    )
    (net (code "48") (name "ETH1_3V3_REG") (class "Default")
      (node (ref "C199") (pin "1") (pinfunction "1_1") (pintype "passive"))
      (node (ref "C200") (pin "1") (pinfunction "1_1") (pintype "passive"))
      (node (ref "C201") (pin "1") (pinfunction "1_1") (pintype "passive"))
      (node (ref "CON9") (pin "11") (pinfunction "A_GRN_11") (pintype "passive"))
      (node (ref "D43") (pin "1") (pinfunction "Cathode_1") (pintype "passive"))
      (node (ref "R238") (pin "2") (pinfunction "2_2") (pintype "passive"))
      (node (ref "R250") (pin "2") (pinfunction "2_2") (pintype "passive"))
      (node (ref "R258") (pin "2") (pinfunction "2_2") (pintype "passive"))
      (node (ref "R259") (pin "2") (pinfunction "2_2") (pintype "passive"))
      (node (ref "R260") (pin "2") (pinfunction "2_2") (pintype "passive"))
      (node (ref "R271") (pin "2") (pinfunction "2_2") (pintype "passive"))
      (node (ref "U44") (pin "29") (pinfunction "DVDD33_29") (pintype "power_in"))
    )
    (net (code "49") (name "GND") (class "Default")
      (node (ref "C184") (pin "1") (pinfunction "1_1") (pintype "passive"))
      (node (ref "C185") (pin "1") (pinfunction "1_1") (pintype "passive"))
      (node (ref "C186") (pin "1") (pinfunction "1_1") (pintype "passive"))
      (node (ref "C187") (pin "2") (pinfunction "2_2") (pintype "passive"))
      (node (ref "C188") (pin "2") (pinfunction "2_2") (pintype "passive"))
      (node (ref "C191") (pin "2") (pinfunction "2_2") (pintype "passive"))
      (node (ref "C192") (pin "2") (pinfunction "2_2") (pintype "passive"))
      (node (ref "C193") (pin "2") (pinfunction "2_2") (pintype "passive"))
      (node (ref "C194") (pin "2") (pinfunction "2_2") (pintype "passive"))
      (node (ref "C195") (pin "2") (pinfunction "2_2") (pintype "passive"))
      (node (ref "C196") (pin "2") (pinfunction "2_2") (pintype "passive"))
      (node (ref "C197") (pin "2") (pinfunction "2_2") (pintype "passive"))
      (node (ref "C198") (pin "2") (pinfunction "2_2") (pintype "passive"))
      (node (ref "C199") (pin "2") (pinfunction "2_2") (pintype "passive"))
      (node (ref "C200") (pin "2") (pinfunction "2_2") (pintype "passive"))
      (node (ref "C201") (pin "2") (pinfunction "2_2") (pintype "passive"))
      (node (ref "C202") (pin "2") (pinfunction "2_2") (pintype "passive"))
      (node (ref "C203") (pin "2") (pinfunction "2_2") (pintype "passive"))
      (node (ref "C204") (pin "2") (pinfunction "2_2") (pintype "passive"))
      (node (ref "C205") (pin "2") (pinfunction "2_2") (pintype "passive"))
      (node (ref "FB12") (pin "2") (pinfunction "2_2") (pintype "passive"))
      (node (ref "R241") (pin "2") (pinfunction "2_2") (pintype "passive"))
      (node (ref "R262") (pin "1") (pinfunction "1_1") (pintype "passive"))
      (node (ref "R263") (pin "1") (pinfunction "1_1") (pintype "passive"))
      (node (ref "R264") (pin "1") (pinfunction "1_1") (pintype "passive"))
      (node (ref "R265") (pin "1") (pinfunction "1_1") (pintype "passive"))
      (node (ref "R266") (pin "1") (pinfunction "1_1") (pintype "passive"))
      (node (ref "R267") (pin "1") (pinfunction "1_1") (pintype "passive"))
      (node (ref "R268") (pin "1") (pinfunction "1_1") (pintype "passive"))
      (node (ref "R269") (pin "1") (pinfunction "1_1") (pintype "passive"))
      (node (ref "R270") (pin "1") (pinfunction "1_1") (pintype "passive"))
      (node (ref "U44") (pin "41") (pinfunction "EPAD_41") (pintype "power_in"))
      (node (ref "Y4") (pin "2") (pinfunction "2_2") (pintype "passive"))
      (node (ref "Y4") (pin "4") (pinfunction "4_4") (pintype "passive"))
    )
    (net (code "50") (name "Net-(CON9-A_YLW)") (class "Default")
      (node (ref "CON9") (pin "13") (pinfunction "A_YLW_13") (pintype "passive"))
      (node (ref "FB12") (pin "1") (pinfunction "1_1") (pintype "passive"))
    )
    (net (code "51") (name "Net-(CON9-C_GRN)") (class "Default")
      (node (ref "C189") (pin "2") (pinfunction "2_2") (pintype "passive"))
      (node (ref "CON9") (pin "12") (pinfunction "C_GRN_12") (pintype "passive"))
      (node (ref "D41") (pin "2") (pinfunction "CATHODE2_2") (pintype "passive"))
      (node (ref "R242") (pin "2") (pinfunction "2_2") (pintype "passive"))
    )
    (net (code "52") (name "Net-(CON9-C_YLW)") (class "Default")
      (node (ref "C190") (pin "2") (pinfunction "2_2") (pintype "passive"))
      (node (ref "CON9") (pin "14") (pinfunction "C_YLW_14") (pintype "passive"))
      (node (ref "D42") (pin "2") (pinfunction "CATHODE2_2") (pintype "passive"))
      (node (ref "R243") (pin "2") (pinfunction "2_2") (pintype "passive"))
    )
    (net (code "53") (name "Net-(CON9-VCC)") (class "Default")
      (node (ref "C184") (pin "2") (pinfunction "2_2") (pintype "passive"))
      (node (ref "CON9") (pin "1") (pinfunction "VCC_1") (pintype "passive"))
    )
    (net (code "54") (name "Net-(TP13-TP)") (class "Default")
      (node (ref "TP13") (pin "1") (pinfunction "TP_1") (pintype "passive"))
      (node (ref "U44") (pin "35") (pinfunction "CLKOUT_35") (pintype "passive"))
    )
    (net (code "55") (name "Net-(U44-INT_N{slash}PME_N)") (class "Default")
      (node (ref "R238") (pin "1") (pinfunction "1_1") (pintype "passive"))
      (node (ref "U44") (pin "31") (pinfunction "INT_N/PME_N_31") (pintype "passive"))
    )
    (net (code "56") (name "Net-(U44-RBIAS)") (class "Default")
      (node (ref "R241") (pin "1") (pinfunction "1_1") (pintype "passive"))
      (node (ref "U44") (pin "39") (pinfunction "RBIAS_39") (pintype "passive"))
    )
    (net (code "57") (name "Net-(U44-REG_O{slash}LDO_O{slash}NC)") (class "Default")
      (node (ref "L15") (pin "1") (pinfunction "1_1") (pintype "passive"))
      (node (ref "U44") (pin "30") (pinfunction "REG_O/LDO_O/NC_30") (pintype "power_in"))
    )
    (net (code "58") (name "VDD_1V8_MAIN") (class "Default")
      (node (ref "R261") (pin "1") (pinfunction "1_1") (pintype "passive"))
    )
    (net (code "59") (name "VDD_3V3_ETH1") (class "Default")
      (node (ref "C204") (pin "1") (pinfunction "1_1") (pintype "passive"))
      (node (ref "C205") (pin "1") (pinfunction "1_1") (pintype "passive"))
      (node (ref "FB13") (pin "2") (pinfunction "2_2") (pintype "passive"))
      (node (ref "R271") (pin "1") (pinfunction "1_1") (pintype "passive"))
      (node (ref "R272") (pin "1") (pinfunction "1_1") (pintype "passive"))
    )
    (net (code "60") (name "VDD_3V3_MAIN") (class "Default")
      (node (ref "FB13") (pin "1") (pinfunction "1_1") (pintype "passive"))
    )
    (net (code "61") (name "XL9555_P01{slash}RGMII1_RST{slash}3V3") (class "Default")
      (node (ref "C192") (pin "1") (pinfunction "1_1") (pintype "passive"))
      (node (ref "D43") (pin "2") (pinfunction "Anode_2") (pintype "passive"))
      (node (ref "R250") (pin "1") (pinfunction "1_1") (pintype "passive"))
      (node (ref "U44") (pin "12") (pinfunction "RESET_N_12") (pintype "passive"))
    )
    (net (code "62") (name "unconnected-(CON9-MH1-Pad15)") (class "Default")
      (node (ref "CON9") (pin "15") (pinfunction "MH1_15") (pintype "passive+no_connect"))
    )
    (net (code "63") (name "unconnected-(CON9-MH2-Pad16)") (class "Default")
      (node (ref "CON9") (pin "16") (pinfunction "MH2_16") (pintype "passive+no_connect"))
    )
  )
)
